# Hauptsignal.net
KiCad netlist of a schematic drawn in EAGLE
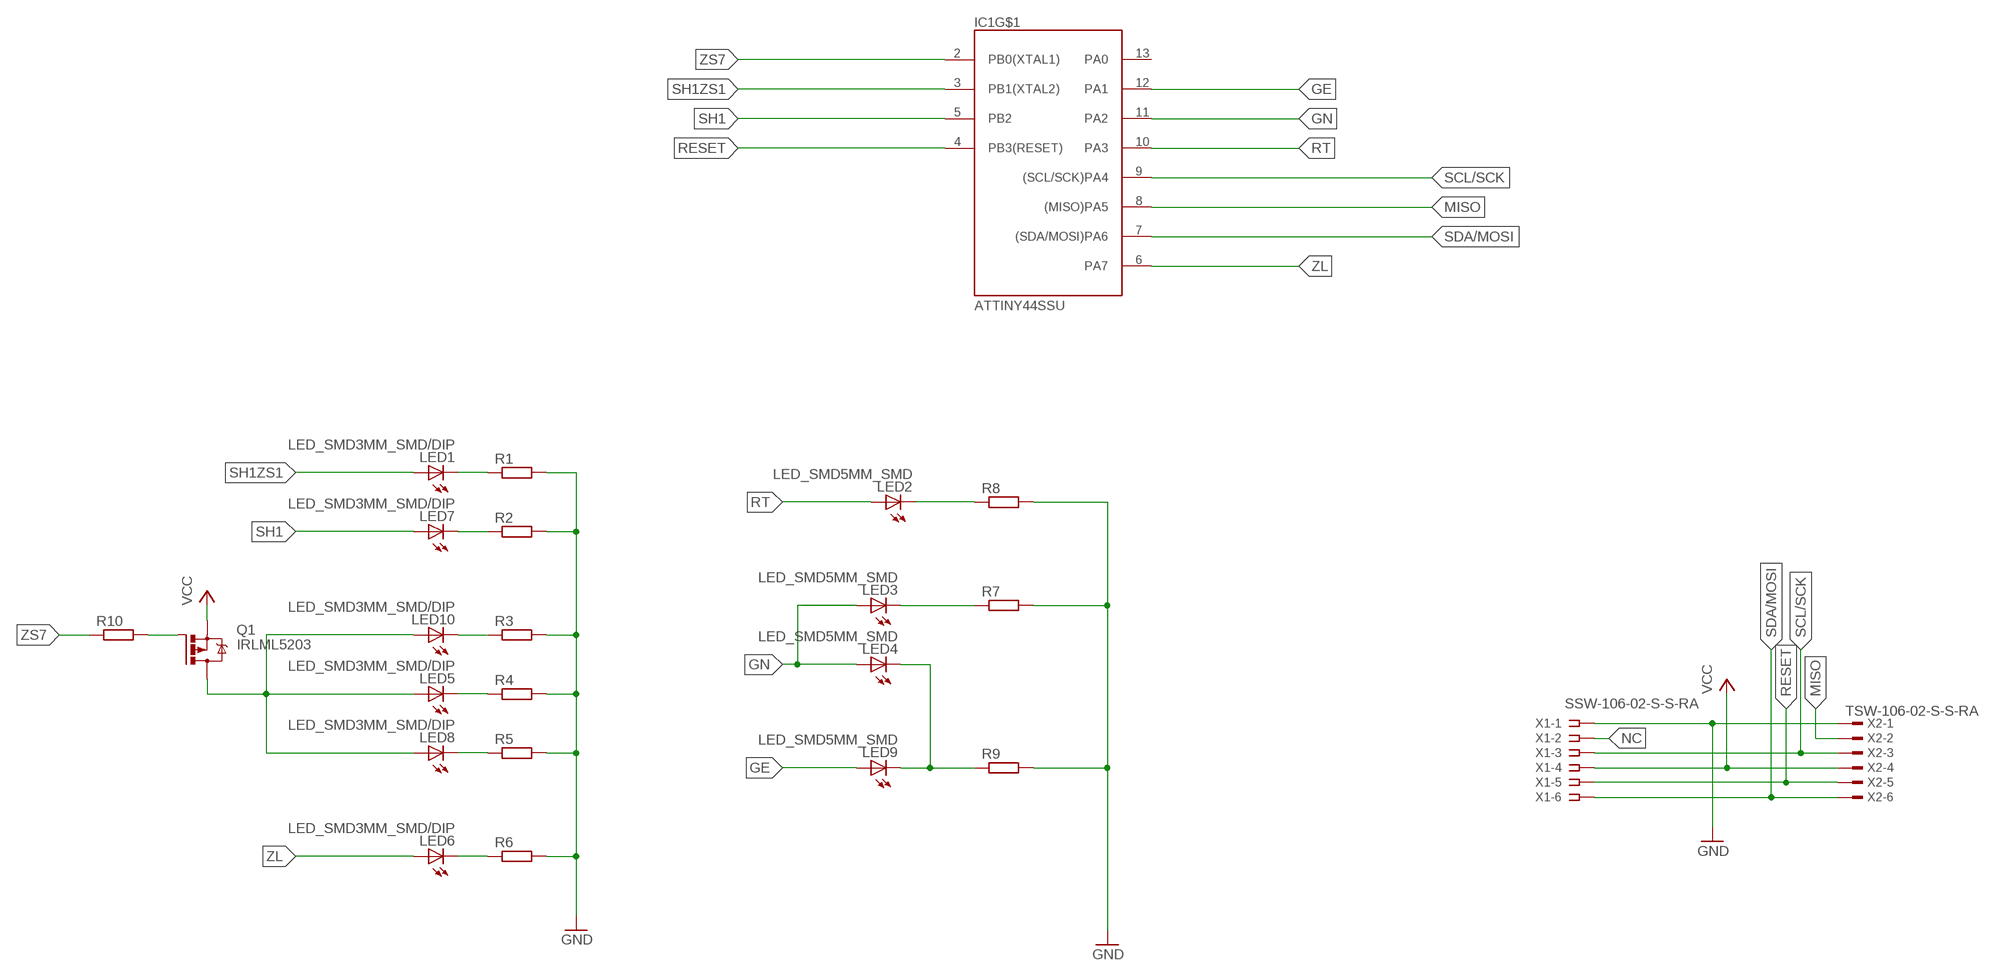
[diagram p0: schematic, sheet 1]

(export (version "E")
  (design (tool "Eeschema 10.0.6"))
  (components
    (comp (ref "IC1")
      (value "ATTINY44SSU")
      (footprint "eagle-import:SO14")
      (libsource (lib "eagle-import") (part "ATTINY44SSU"))
    )
    (comp (ref "LED1")
      (value "LED_SMD3MM_SMD/DIP")
      (footprint "eagle-import:3MM_FLAT_DIP_SMDLED")
      (libsource (lib "eagle-import") (part "LED_SMD3MM_SMD/DIP"))
    )
    (comp (ref "LED2")
      (value "LED_SMD5MM_SMD")
      (footprint "eagle-import:5MM_FLAT_SMDLED")
      (libsource (lib "eagle-import") (part "LED_SMD5MM_SMD"))
    )
    (comp (ref "LED3")
      (value "LED_SMD5MM_SMD")
      (footprint "eagle-import:5MM_FLAT_SMDLED")
      (libsource (lib "eagle-import") (part "LED_SMD5MM_SMD"))
    )
    (comp (ref "LED4")
      (value "LED_SMD5MM_SMD")
      (footprint "eagle-import:5MM_FLAT_SMDLED")
      (libsource (lib "eagle-import") (part "LED_SMD5MM_SMD"))
    )
    (comp (ref "LED5")
      (value "LED_SMD3MM_SMD/DIP")
      (footprint "eagle-import:3MM_FLAT_DIP_SMDLED")
      (libsource (lib "eagle-import") (part "LED_SMD3MM_SMD/DIP"))
    )
    (comp (ref "LED6")
      (value "LED_SMD3MM_SMD/DIP")
      (footprint "eagle-import:3MM_FLAT_DIP_SMDLED")
      (libsource (lib "eagle-import") (part "LED_SMD3MM_SMD/DIP"))
    )
    (comp (ref "LED7")
      (value "LED_SMD3MM_SMD/DIP")
      (footprint "eagle-import:3MM_FLAT_DIP_SMDLED")
      (libsource (lib "eagle-import") (part "LED_SMD3MM_SMD/DIP"))
    )
    (comp (ref "LED8")
      (value "LED_SMD3MM_SMD/DIP")
      (footprint "eagle-import:3MM_FLAT_DIP_SMDLED")
      (libsource (lib "eagle-import") (part "LED_SMD3MM_SMD/DIP"))
    )
    (comp (ref "LED9")
      (value "LED_SMD5MM_SMD")
      (footprint "eagle-import:5MM_FLAT_SMDLED")
      (libsource (lib "eagle-import") (part "LED_SMD5MM_SMD"))
    )
    (comp (ref "LED10")
      (value "LED_SMD3MM_SMD/DIP")
      (footprint "eagle-import:3MM_FLAT_DIP_SMDLED")
      (libsource (lib "eagle-import") (part "LED_SMD3MM_SMD/DIP"))
    )
    (comp (ref "Q1")
      (value "IRLML5203")
      (footprint "eagle-import:MICRO3")
      (libsource (lib "eagle-import") (part "IRLML5203"))
    )
    (comp (ref "R1")
      (value "R-EU_R0603")
      (footprint "eagle-import:R0603")
      (libsource (lib "eagle-import") (part "R-EU_R0603"))
    )
    (comp (ref "R2")
      (value "R-EU_R0603")
      (footprint "eagle-import:R0603")
      (libsource (lib "eagle-import") (part "R-EU_R0603"))
    )
    (comp (ref "R3")
      (value "R-EU_R0603")
      (footprint "eagle-import:R0603")
      (libsource (lib "eagle-import") (part "R-EU_R0603"))
    )
    (comp (ref "R4")
      (value "R-EU_R0603")
      (footprint "eagle-import:R0603")
      (libsource (lib "eagle-import") (part "R-EU_R0603"))
    )
    (comp (ref "R5")
      (value "R-EU_R0603")
      (footprint "eagle-import:R0603")
      (libsource (lib "eagle-import") (part "R-EU_R0603"))
    )
    (comp (ref "R6")
      (value "R-EU_R0603")
      (footprint "eagle-import:R0603")
      (libsource (lib "eagle-import") (part "R-EU_R0603"))
    )
    (comp (ref "R7")
      (value "R-EU_R0603")
      (footprint "eagle-import:R0603")
      (libsource (lib "eagle-import") (part "R-EU_R0603"))
    )
    (comp (ref "R8")
      (value "R-EU_R0603")
      (footprint "eagle-import:R0603")
      (libsource (lib "eagle-import") (part "R-EU_R0603"))
    )
    (comp (ref "R9")
      (value "R-EU_R0603")
      (footprint "eagle-import:R0603")
      (libsource (lib "eagle-import") (part "R-EU_R0603"))
    )
    (comp (ref "R10")
      (value "R-EU_R0603")
      (footprint "eagle-import:R0603")
      (libsource (lib "eagle-import") (part "R-EU_R0603"))
    )
    (comp (ref "X1")
      (value "SSW-106-02-S-S-RA")
      (footprint "eagle-import:SSW-106-02-S-S-RA")
      (libsource (lib "eagle-import") (part "SSW-106-02-S-S-RA"))
    )
    (comp (ref "X2")
      (value "TSW-106-02-S-S-RA")
      (footprint "eagle-import:TSW-106-02-S-S-RA")
      (libsource (lib "eagle-import") (part "TSW-106-02-S-S-RA"))
    )
  )
  (nets
    (net (code "1") (name "GE") (class "Default")
      (node (ref "IC1") (pin "12") (pinfunction "PA1_12") (pintype "bidirectional"))
      (node (ref "LED9") (pin "+") (pinfunction "A_+") (pintype "passive"))
    )
    (net (code "2") (name "GN") (class "Default")
      (node (ref "IC1") (pin "11") (pinfunction "PA2_11") (pintype "bidirectional"))
      (node (ref "LED3") (pin "+") (pinfunction "A_+") (pintype "passive"))
      (node (ref "LED4") (pin "+") (pinfunction "A_+") (pintype "passive"))
    )
    (net (code "3") (name "GND") (class "Default")
      (node (ref "R1") (pin "2") (pinfunction "2_2") (pintype "passive"))
      (node (ref "R2") (pin "2") (pinfunction "2_2") (pintype "passive"))
      (node (ref "R3") (pin "2") (pinfunction "2_2") (pintype "passive"))
      (node (ref "R4") (pin "2") (pinfunction "2_2") (pintype "passive"))
      (node (ref "R5") (pin "2") (pinfunction "2_2") (pintype "passive"))
      (node (ref "R6") (pin "2") (pinfunction "2_2") (pintype "passive"))
      (node (ref "R7") (pin "2") (pinfunction "2_2") (pintype "passive"))
      (node (ref "R8") (pin "2") (pinfunction "2_2") (pintype "passive"))
      (node (ref "R9") (pin "2") (pinfunction "2_2") (pintype "passive"))
      (node (ref "X1") (pin "1") (pinfunction "1_1") (pintype "passive"))
      (node (ref "X2") (pin "1") (pinfunction "1_1") (pintype "passive"))
    )
    (net (code "4") (name "MISO") (class "Default")
      (node (ref "IC1") (pin "8") (pinfunction "(MISO)PA5_8") (pintype "bidirectional"))
      (node (ref "X2") (pin "2") (pinfunction "1_2") (pintype "passive"))
    )
    (net (code "5") (name "NC") (class "Default")
      (node (ref "X1") (pin "2") (pinfunction "1_2") (pintype "passive"))
    )
    (net (code "6") (name "Net-(LED1-C)") (class "Default")
      (node (ref "LED1") (pin "-") (pinfunction "C_-") (pintype "passive"))
      (node (ref "R1") (pin "1") (pinfunction "1_1") (pintype "passive"))
    )
    (net (code "7") (name "Net-(LED2-C)") (class "Default")
      (node (ref "LED2") (pin "-") (pinfunction "C_-") (pintype "passive"))
      (node (ref "R8") (pin "1") (pinfunction "1_1") (pintype "passive"))
    )
    (net (code "8") (name "Net-(LED3-C)") (class "Default")
      (node (ref "LED3") (pin "-") (pinfunction "C_-") (pintype "passive"))
      (node (ref "R7") (pin "1") (pinfunction "1_1") (pintype "passive"))
    )
    (net (code "9") (name "Net-(LED4-C)") (class "Default")
      (node (ref "LED4") (pin "-") (pinfunction "C_-") (pintype "passive"))
      (node (ref "LED9") (pin "-") (pinfunction "C_-") (pintype "passive"))
      (node (ref "R9") (pin "1") (pinfunction "1_1") (pintype "passive"))
    )
    (net (code "10") (name "Net-(LED5-C)") (class "Default")
      (node (ref "LED5") (pin "-") (pinfunction "C_-") (pintype "passive"))
      (node (ref "R4") (pin "1") (pinfunction "1_1") (pintype "passive"))
    )
    (net (code "11") (name "Net-(LED6-C)") (class "Default")
      (node (ref "LED6") (pin "-") (pinfunction "C_-") (pintype "passive"))
      (node (ref "R6") (pin "1") (pinfunction "1_1") (pintype "passive"))
    )
    (net (code "12") (name "Net-(LED7-C)") (class "Default")
      (node (ref "LED7") (pin "-") (pinfunction "C_-") (pintype "passive"))
      (node (ref "R2") (pin "1") (pinfunction "1_1") (pintype "passive"))
    )
    (net (code "13") (name "Net-(LED8-C)") (class "Default")
      (node (ref "LED8") (pin "-") (pinfunction "C_-") (pintype "passive"))
      (node (ref "R5") (pin "1") (pinfunction "1_1") (pintype "passive"))
    )
    (net (code "14") (name "Net-(LED10-A)") (class "Default")
      (node (ref "LED10") (pin "+") (pinfunction "A_+") (pintype "passive"))
      (node (ref "LED5") (pin "+") (pinfunction "A_+") (pintype "passive"))
      (node (ref "LED8") (pin "+") (pinfunction "A_+") (pintype "passive"))
      (node (ref "Q1") (pin "3") (pinfunction "D_3") (pintype "passive"))
    )
    (net (code "15") (name "Net-(LED10-C)") (class "Default")
      (node (ref "LED10") (pin "-") (pinfunction "C_-") (pintype "passive"))
      (node (ref "R3") (pin "1") (pinfunction "1_1") (pintype "passive"))
    )
    (net (code "16") (name "Net-(Q1-G)") (class "Default")
      (node (ref "Q1") (pin "1") (pinfunction "G_1") (pintype "passive"))
      (node (ref "R10") (pin "2") (pinfunction "2_2") (pintype "passive"))
    )
    (net (code "17") (name "RESET") (class "Default")
      (node (ref "IC1") (pin "4") (pinfunction "PB3(RESET)_4") (pintype "bidirectional"))
      (node (ref "X1") (pin "5") (pinfunction "1_5") (pintype "passive"))
      (node (ref "X2") (pin "5") (pinfunction "1_5") (pintype "passive"))
    )
    (net (code "18") (name "RT") (class "Default")
      (node (ref "IC1") (pin "10") (pinfunction "PA3_10") (pintype "bidirectional"))
      (node (ref "LED2") (pin "+") (pinfunction "A_+") (pintype "passive"))
    )
    (net (code "19") (name "SCL{slash}SCK") (class "Default")
      (node (ref "IC1") (pin "9") (pinfunction "(SCL/SCK)PA4_9") (pintype "bidirectional"))
      (node (ref "X1") (pin "3") (pinfunction "1_3") (pintype "passive"))
      (node (ref "X2") (pin "3") (pinfunction "1_3") (pintype "passive"))
    )
    (net (code "20") (name "SDA{slash}MOSI") (class "Default")
      (node (ref "IC1") (pin "7") (pinfunction "(SDA/MOSI)PA6_7") (pintype "bidirectional"))
      (node (ref "X1") (pin "6") (pinfunction "1_6") (pintype "passive"))
      (node (ref "X2") (pin "6") (pinfunction "1_6") (pintype "passive"))
    )
    (net (code "21") (name "SH1") (class "Default")
      (node (ref "IC1") (pin "5") (pinfunction "PB2_5") (pintype "bidirectional"))
      (node (ref "LED7") (pin "+") (pinfunction "A_+") (pintype "passive"))
    )
    (net (code "22") (name "SH1ZS1") (class "Default")
      (node (ref "IC1") (pin "3") (pinfunction "PB1(XTAL2)_3") (pintype "bidirectional"))
      (node (ref "LED1") (pin "+") (pinfunction "A_+") (pintype "passive"))
    )
    (net (code "23") (name "VCC") (class "Default")
      (node (ref "Q1") (pin "2") (pinfunction "S_2") (pintype "passive"))
      (node (ref "X1") (pin "4") (pinfunction "1_4") (pintype "passive"))
      (node (ref "X2") (pin "4") (pinfunction "1_4") (pintype "passive"))
    )
    (net (code "24") (name "ZL") (class "Default")
      (node (ref "IC1") (pin "6") (pinfunction "PA7_6") (pintype "bidirectional"))
      (node (ref "LED6") (pin "+") (pinfunction "A_+") (pintype "passive"))
    )
    (net (code "25") (name "ZS7") (class "Default")
      (node (ref "IC1") (pin "2") (pinfunction "PB0(XTAL1)_2") (pintype "bidirectional"))
      (node (ref "R10") (pin "1") (pinfunction "1_1") (pintype "passive"))
    )
    (net (code "26") (name "unconnected-(IC1A-PA0-Pad13)") (class "Default")
      (node (ref "IC1") (pin "13") (pinfunction "PA0_13") (pintype "bidirectional"))
    )
  )
)
